# Sheet1.net
KiCad netlist of a schematic drawn in Altium Designer
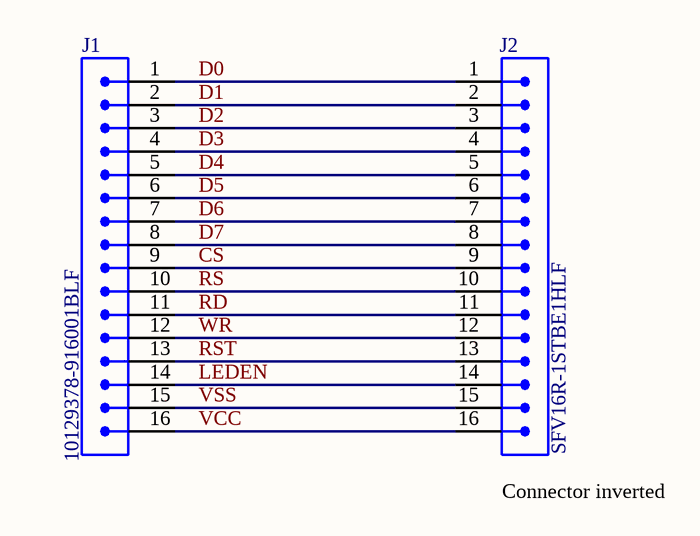
[diagram p0: Sheet1.SchDoc]

(export (version "E")
  (design (tool "Eeschema 10.0.6"))
  (components
    (comp (ref "J1")
      (value "10129378-916001BLF")
      (footprint "16POS")
      (description "Connector Header Through Hole 16 position 0.100\" (2.54mm)")
      (libsource (lib "Amphenol ICC (FCI)") (part "10129378-916001BLF"))
    )
    (comp (ref "J2")
      (value "SFV16R-1STBE1HLF")
      (footprint "FFC16POS")
      (description "16 Position FFC, FPC Connector Contacts, Bottom 0.020\" (0.50mm) Surface Mount, Right Angle")
      (libsource (lib "Amphenol ICC (FCI)") (part "SFV16R-1STBE1HLF"))
    )
  )
  (nets
    (net (code "1") (name "/D0") (class "Default")
      (node (ref "J1") (pin "1") (pinfunction "1_1") (pintype "passive"))
      (node (ref "J2") (pin "1") (pinfunction "1_1") (pintype "passive"))
    )
    (net (code "2") (name "/D1") (class "Default")
      (node (ref "J1") (pin "2") (pinfunction "2_2") (pintype "passive"))
      (node (ref "J2") (pin "2") (pinfunction "2_2") (pintype "passive"))
    )
    (net (code "3") (name "/D2") (class "Default")
      (node (ref "J1") (pin "3") (pinfunction "3_3") (pintype "passive"))
      (node (ref "J2") (pin "3") (pinfunction "3_3") (pintype "passive"))
    )
    (net (code "4") (name "/D3") (class "Default")
      (node (ref "J1") (pin "4") (pinfunction "4_4") (pintype "passive"))
      (node (ref "J2") (pin "4") (pinfunction "4_4") (pintype "passive"))
    )
    (net (code "5") (name "/D4") (class "Default")
      (node (ref "J1") (pin "5") (pinfunction "5_5") (pintype "passive"))
      (node (ref "J2") (pin "5") (pinfunction "5_5") (pintype "passive"))
    )
    (net (code "6") (name "/D5") (class "Default")
      (node (ref "J1") (pin "6") (pinfunction "6_6") (pintype "passive"))
      (node (ref "J2") (pin "6") (pinfunction "6_6") (pintype "passive"))
    )
    (net (code "7") (name "/D6") (class "Default")
      (node (ref "J1") (pin "7") (pinfunction "7_7") (pintype "passive"))
      (node (ref "J2") (pin "7") (pinfunction "7_7") (pintype "passive"))
    )
    (net (code "8") (name "/D7") (class "Default")
      (node (ref "J1") (pin "8") (pinfunction "8_8") (pintype "passive"))
      (node (ref "J2") (pin "8") (pinfunction "8_8") (pintype "passive"))
    )
    (net (code "9") (name "/LEDEN") (class "Default")
      (node (ref "J1") (pin "14") (pinfunction "14_14") (pintype "passive"))
      (node (ref "J2") (pin "14") (pinfunction "14_14") (pintype "passive"))
    )
    (net (code "10") (name "/VCC") (class "Default")
      (node (ref "J1") (pin "16") (pinfunction "16_16") (pintype "passive"))
      (node (ref "J2") (pin "16") (pinfunction "16_16") (pintype "passive"))
    )
    (net (code "11") (name "/VSS") (class "Default")
      (node (ref "J1") (pin "15") (pinfunction "15_15") (pintype "passive"))
      (node (ref "J2") (pin "15") (pinfunction "15_15") (pintype "passive"))
    )
    (net (code "12") (name "/~{CS}") (class "Default")
      (node (ref "J1") (pin "9") (pinfunction "9_9") (pintype "passive"))
      (node (ref "J2") (pin "9") (pinfunction "9_9") (pintype "passive"))
    )
    (net (code "13") (name "/~{RD}") (class "Default")
      (node (ref "J1") (pin "11") (pinfunction "11_11") (pintype "passive"))
      (node (ref "J2") (pin "11") (pinfunction "11_11") (pintype "passive"))
    )
    (net (code "14") (name "/~{RST}") (class "Default")
      (node (ref "J1") (pin "13") (pinfunction "13_13") (pintype "passive"))
      (node (ref "J2") (pin "13") (pinfunction "13_13") (pintype "passive"))
    )
    (net (code "15") (name "/~{RS}") (class "Default")
      (node (ref "J1") (pin "10") (pinfunction "10_10") (pintype "passive"))
      (node (ref "J2") (pin "10") (pinfunction "10_10") (pintype "passive"))
    )
    (net (code "16") (name "/~{WR}") (class "Default")
      (node (ref "J1") (pin "12") (pinfunction "12_12") (pintype "passive"))
      (node (ref "J2") (pin "12") (pinfunction "12_12") (pintype "passive"))
    )
  )
)
